# queso_dip_v4_5.net
KiCad netlist of a schematic drawn in EAGLE
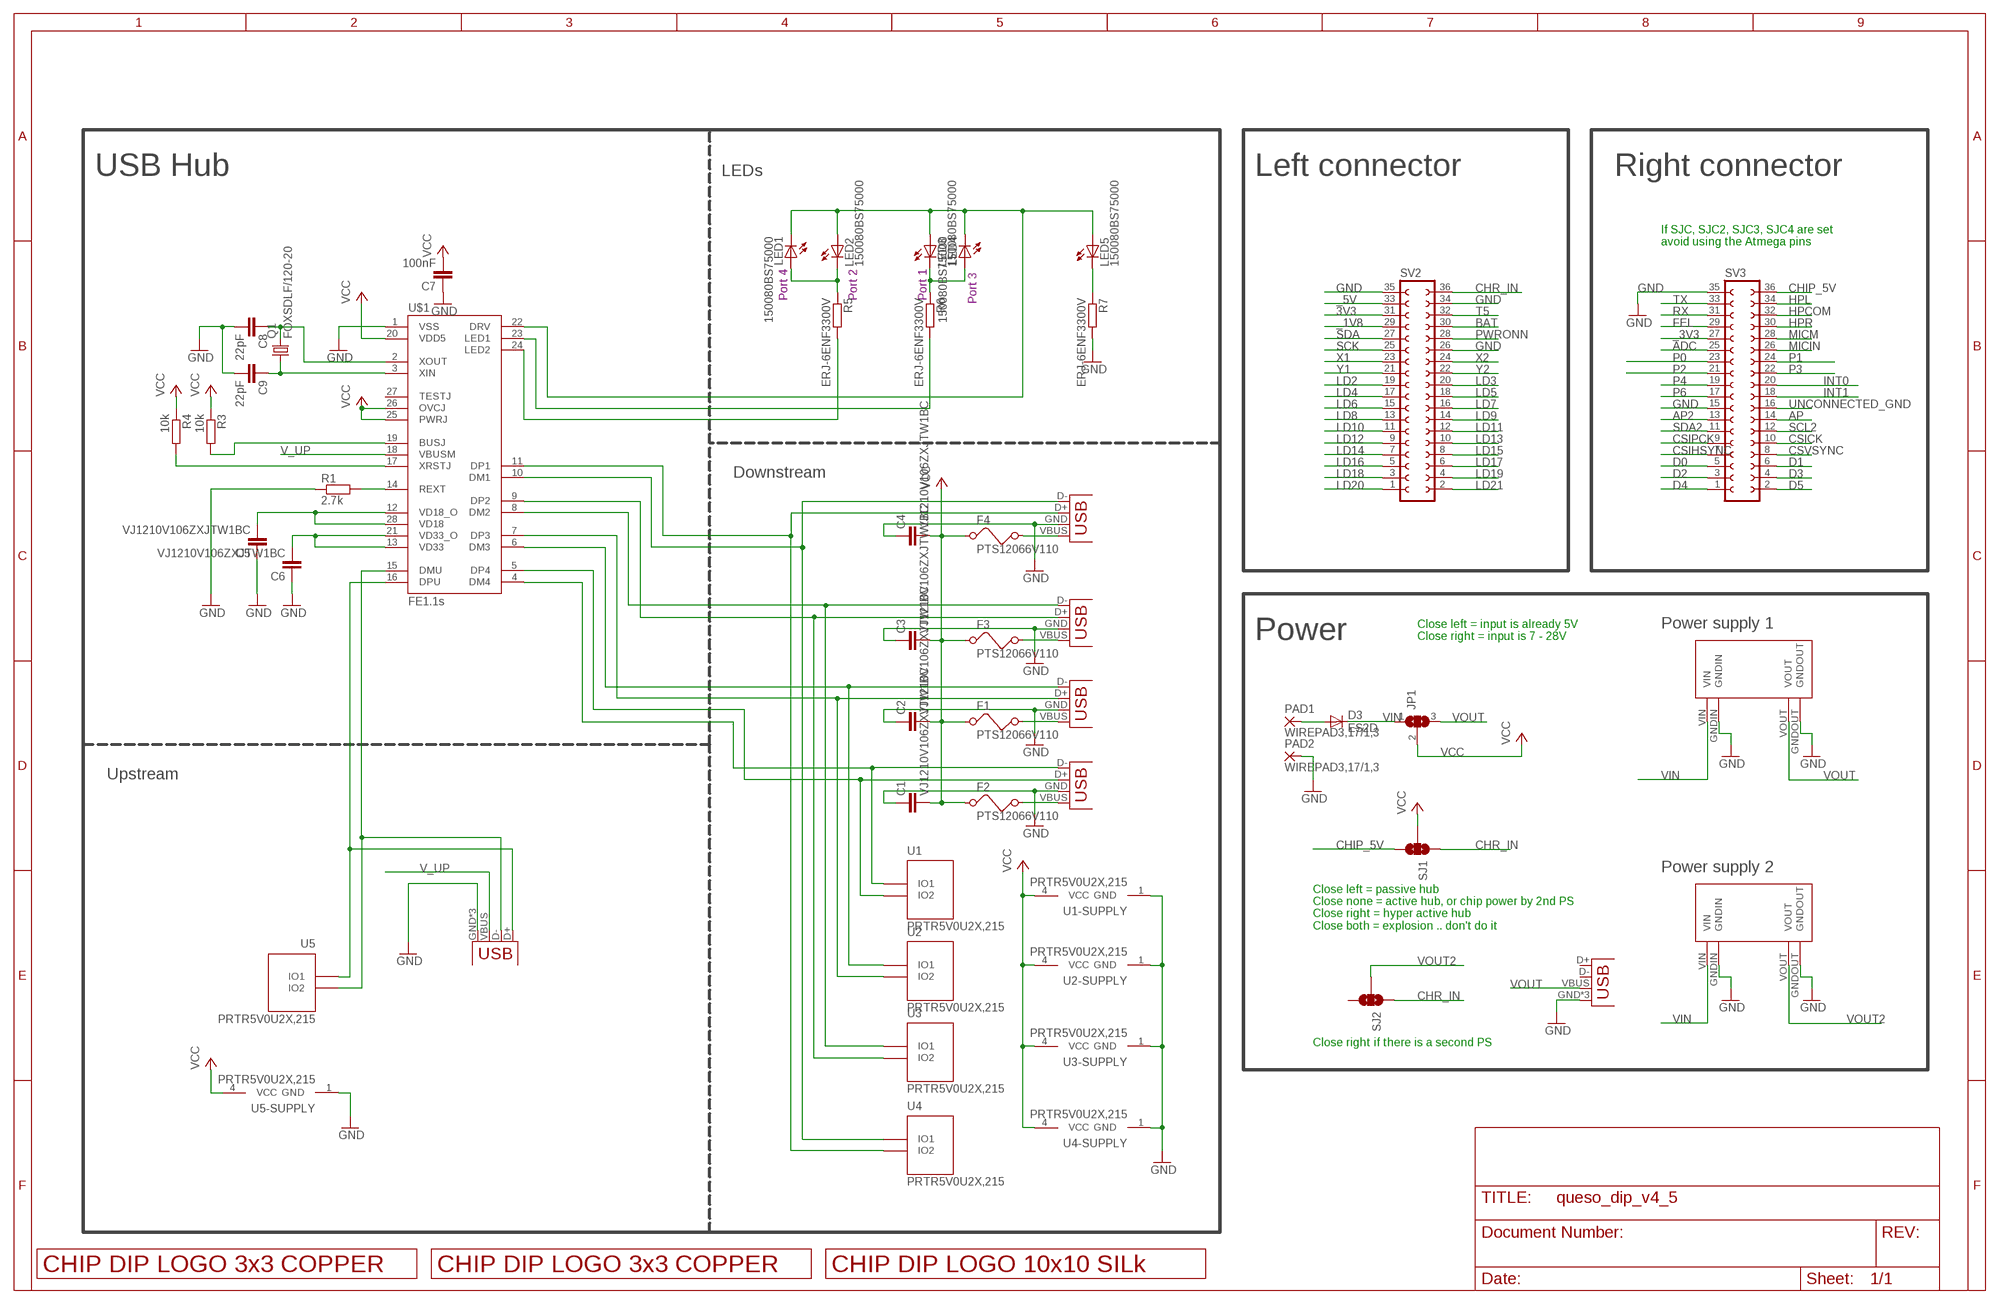
[diagram p0: schematic, sheet 1]

(export (version "E")
  (design (tool "Eeschema 10.0.6"))
  (components
    (comp (ref "C1")
      (value "VJ1210V106ZXJTW1BC")
      (footprint "eagle-import:C1210")
      (libsource (lib "eagle-import") (part "C-EUC1210"))
    )
    (comp (ref "C2")
      (value "VJ1210V106ZXJTW1BC")
      (footprint "eagle-import:C1210")
      (libsource (lib "eagle-import") (part "C-EUC1210"))
    )
    (comp (ref "C3")
      (value "VJ1210V106ZXJTW1BC")
      (footprint "eagle-import:C1210")
      (libsource (lib "eagle-import") (part "C-EUC1210"))
    )
    (comp (ref "C4")
      (value "VJ1210V106ZXJTW1BC")
      (footprint "eagle-import:C1210")
      (libsource (lib "eagle-import") (part "C-EUC1210"))
    )
    (comp (ref "C5")
      (value "VJ1210V106ZXJTW1BC")
      (footprint "eagle-import:C1210")
      (libsource (lib "eagle-import") (part "C-EUC1210"))
    )
    (comp (ref "C6")
      (value "VJ1210V106ZXJTW1BC")
      (footprint "eagle-import:C1210")
      (libsource (lib "eagle-import") (part "C-EUC1210"))
    )
    (comp (ref "C7")
      (value "100nF")
      (footprint "eagle-import:C0805")
      (libsource (lib "eagle-import") (part "C-EUC0805"))
    )
    (comp (ref "C8")
      (value "22pF")
      (footprint "eagle-import:C0805")
      (libsource (lib "eagle-import") (part "C-EUC0805"))
    )
    (comp (ref "C9")
      (value "22pF")
      (footprint "eagle-import:C0805")
      (libsource (lib "eagle-import") (part "C-EUC0805"))
    )
    (comp (ref "D3")
      (value "ES2D")
      (footprint "eagle-import:SMB")
      (libsource (lib "eagle-import") (part "ES2D"))
    )
    (comp (ref "F1")
      (value "PTS12066V110")
      (footprint "eagle-import:1210")
      (libsource (lib "eagle-import") (part "FUSED"))
    )
    (comp (ref "F2")
      (value "PTS12066V110")
      (footprint "eagle-import:1210")
      (libsource (lib "eagle-import") (part "FUSED"))
    )
    (comp (ref "F3")
      (value "PTS12066V110")
      (footprint "eagle-import:1210")
      (libsource (lib "eagle-import") (part "FUSED"))
    )
    (comp (ref "F4")
      (value "PTS12066V110")
      (footprint "eagle-import:1210")
      (libsource (lib "eagle-import") (part "FUSED"))
    )
    (comp (ref "JP1")
      (value "SJ2W")
      (footprint "eagle-import:SJ_2")
      (libsource (lib "eagle-import") (part "SJ2W"))
    )
    (comp (ref "LED1")
      (value "150080BS75000")
      (footprint "eagle-import:CHIP-LED0805")
      (libsource (lib "eagle-import") (part "LEDCHIP-LED0805"))
    )
    (comp (ref "LED2")
      (value "150080BS75000")
      (footprint "eagle-import:CHIP-LED0805")
      (libsource (lib "eagle-import") (part "LEDCHIP-LED0805"))
    )
    (comp (ref "LED3")
      (value "150080BS75000")
      (footprint "eagle-import:CHIP-LED0805")
      (libsource (lib "eagle-import") (part "LEDCHIP-LED0805"))
    )
    (comp (ref "LED4")
      (value "150080BS75000")
      (footprint "eagle-import:CHIP-LED0805")
      (libsource (lib "eagle-import") (part "LEDCHIP-LED0805"))
    )
    (comp (ref "LED5")
      (value "150080BS75000")
      (footprint "eagle-import:CHIP-LED0805")
      (libsource (lib "eagle-import") (part "LEDCHIP-LED0805"))
    )
    (comp (ref "PAD1")
      (value "WIREPAD3,17/1,3")
      (footprint "eagle-import:3,17_1,3")
      (libsource (lib "eagle-import") (part "WIREPAD3,17/1,3"))
    )
    (comp (ref "PAD2")
      (value "WIREPAD3,17/1,3")
      (footprint "eagle-import:3,17_1,3")
      (libsource (lib "eagle-import") (part "WIREPAD3,17/1,3"))
    )
    (comp (ref "Q1")
      (value "FOXSDLF/120-20")
      (footprint "eagle-import:SM49")
      (libsource (lib "eagle-import") (part "CRYSTALSM49"))
    )
    (comp (ref "R1")
      (value "2.7k")
      (footprint "eagle-import:R0805")
      (libsource (lib "eagle-import") (part "R-EU_R0805"))
    )
    (comp (ref "R3")
      (value "10k")
      (footprint "eagle-import:R0805")
      (libsource (lib "eagle-import") (part "R-EU_R0805"))
    )
    (comp (ref "R4")
      (value "10k")
      (footprint "eagle-import:R0805")
      (libsource (lib "eagle-import") (part "R-EU_R0805"))
    )
    (comp (ref "R5")
      (value "ERJ-6ENF3300V")
      (footprint "eagle-import:R0805")
      (libsource (lib "eagle-import") (part "R-EU_R0805"))
    )
    (comp (ref "R6")
      (value "ERJ-6ENF3300V")
      (footprint "eagle-import:R0805")
      (libsource (lib "eagle-import") (part "R-EU_R0805"))
    )
    (comp (ref "R7")
      (value "ERJ-6ENF3300V")
      (footprint "eagle-import:R0805")
      (libsource (lib "eagle-import") (part "R-EU_R0805"))
    )
    (comp (ref "SJ1")
      (value "SOLDERJUMPER_2WAYT")
      (footprint "eagle-import:SJ_2")
      (libsource (lib "eagle-import") (part "SOLDERJUMPER_2WAYT"))
    )
    (comp (ref "SJ2")
      (value "SOLDERJUMPER_2WAYT")
      (footprint "eagle-import:SJ_2")
      (libsource (lib "eagle-import") (part "SOLDERJUMPER_2WAYT"))
    )
    (comp (ref "SV2")
      (value "FE18-2")
      (footprint "eagle-import:FE18-2")
      (libsource (lib "eagle-import") (part "FE18-2"))
    )
    (comp (ref "SV3")
      (value "FE18-2")
      (footprint "eagle-import:FE18-2")
      (libsource (lib "eagle-import") (part "FE18-2"))
    )
    (comp (ref "U$1")
      (value "FE1.1S")
      (footprint "eagle-import:FE1.1S_SSOP-28")
      (libsource (lib "eagle-import") (part "FE1.1S"))
    )
    (comp (ref "U$2")
      (value "LOGO_3X3_COPPER")
      (footprint "eagle-import:LOGO_3X3_COPPER")
      (libsource (lib "eagle-import") (part "LOGO_3X3_COPPER"))
    )
    (comp (ref "U$3")
      (value "MP1584EN")
      (footprint "eagle-import:MP1584EN")
      (libsource (lib "eagle-import") (part "MP1584EN"))
    )
    (comp (ref "U$4")
      (value "LOGO_3X3_COPPER")
      (footprint "eagle-import:LOGO_3X3_COPPER")
      (libsource (lib "eagle-import") (part "LOGO_3X3_COPPER"))
    )
    (comp (ref "U$5")
      (value "LOGO_10X10_SILK")
      (footprint "eagle-import:LOGO_10X10_SILK")
      (libsource (lib "eagle-import") (part "LOGO_10X10_SILK"))
    )
    (comp (ref "U$9")
      (value "MP1584EN")
      (footprint "eagle-import:MP1584EN")
      (libsource (lib "eagle-import") (part "MP1584EN"))
    )
    (comp (ref "U1")
      (value "PRTR5V0U2X,215")
      (footprint "eagle-import:SOT-143B")
      (fields (field (name "MANUFACTURER") "NXP Semiconductors"))
      (libsource (lib "eagle-import") (part "PRTR5V0U2X?"))
    )
    (comp (ref "U2")
      (value "PRTR5V0U2X,215")
      (footprint "eagle-import:SOT-143B")
      (fields (field (name "MANUFACTURER") "NXP Semiconductors"))
      (libsource (lib "eagle-import") (part "PRTR5V0U2X?"))
    )
    (comp (ref "U3")
      (value "PRTR5V0U2X,215")
      (footprint "eagle-import:SOT-143B")
      (fields (field (name "MANUFACTURER") "NXP Semiconductors"))
      (libsource (lib "eagle-import") (part "PRTR5V0U2X?"))
    )
    (comp (ref "U4")
      (value "PRTR5V0U2X,215")
      (footprint "eagle-import:SOT-143B")
      (fields (field (name "MANUFACTURER") "NXP Semiconductors"))
      (libsource (lib "eagle-import") (part "PRTR5V0U2X?"))
    )
    (comp (ref "U5")
      (value "PRTR5V0U2X,215")
      (footprint "eagle-import:SOT-143B")
      (fields (field (name "MANUFACTURER") "NXP Semiconductors"))
      (libsource (lib "eagle-import") (part "PRTR5V0U2X?"))
    )
    (comp (ref "USB")
      (value "USBUSB-MICROB-SMT-DIP")
      (footprint "eagle-import:USB-MICROB-SMT-DIP")
      (libsource (lib "eagle-import") (part "USBUSB-MICROB-SMT-DIP"))
    )
    (comp (ref "USB1")
      (value "USBUSB-MICROB-SMT-DIP")
      (footprint "eagle-import:USB-MICROB-SMT-DIP")
      (libsource (lib "eagle-import") (part "USBUSB-MICROB-SMT-DIP"))
    )
    (comp (ref "X1")
      (value "USB-A-HU")
      (footprint "eagle-import:USB-A-HU")
      (libsource (lib "eagle-import") (part "USB-A-HU"))
    )
    (comp (ref "X2")
      (value "USB-A-HU")
      (footprint "eagle-import:USB-A-HU")
      (libsource (lib "eagle-import") (part "USB-A-HU"))
    )
    (comp (ref "X3")
      (value "USB-A-HU")
      (footprint "eagle-import:USB-A-HU")
      (libsource (lib "eagle-import") (part "USB-A-HU"))
    )
    (comp (ref "X4")
      (value "USB-A-HU")
      (footprint "eagle-import:USB-A-HU")
      (libsource (lib "eagle-import") (part "USB-A-HU"))
    )
  )
  (nets
    (net (code "1") (name "/3V3") (class "Default")
      (node (ref "SV2") (pin "31") (pinfunction "31_31") (pintype "passive"))
    )
    (net (code "2") (name "/ADC") (class "Default")
      (node (ref "SV3") (pin "25") (pinfunction "25_25") (pintype "passive"))
    )
    (net (code "3") (name "/AP") (class "Default")
      (node (ref "SV3") (pin "14") (pinfunction "14_14") (pintype "passive"))
    )
    (net (code "4") (name "/AP2") (class "Default")
      (node (ref "SV3") (pin "13") (pinfunction "13_13") (pintype "passive"))
    )
    (net (code "5") (name "/BAT") (class "Default")
      (node (ref "SV2") (pin "30") (pinfunction "30_30") (pintype "passive"))
    )
    (net (code "6") (name "/CHIP_5V") (class "Default")
      (node (ref "SJ1") (pin "3") (pinfunction "3_3") (pintype "passive"))
      (node (ref "SV3") (pin "36") (pinfunction "36_36") (pintype "passive"))
    )
    (net (code "7") (name "/CHR_IN") (class "Default")
      (node (ref "SJ1") (pin "1") (pinfunction "1_1") (pintype "passive"))
      (node (ref "SJ2") (pin "1") (pinfunction "1_1") (pintype "passive"))
      (node (ref "SV2") (pin "36") (pinfunction "36_36") (pintype "passive"))
    )
    (net (code "8") (name "/CSICK") (class "Default")
      (node (ref "SV3") (pin "10") (pinfunction "10_10") (pintype "passive"))
    )
    (net (code "9") (name "/CSIHSYNC") (class "Default")
      (node (ref "SV3") (pin "7") (pinfunction "7_7") (pintype "passive"))
    )
    (net (code "10") (name "/CSIPCK") (class "Default")
      (node (ref "SV3") (pin "9") (pinfunction "9_9") (pintype "passive"))
    )
    (net (code "11") (name "/CSVSYNC") (class "Default")
      (node (ref "SV3") (pin "8") (pinfunction "8_8") (pintype "passive"))
    )
    (net (code "12") (name "/D0") (class "Default")
      (node (ref "SV3") (pin "5") (pinfunction "5_5") (pintype "passive"))
    )
    (net (code "13") (name "/D1") (class "Default")
      (node (ref "SV3") (pin "6") (pinfunction "6_6") (pintype "passive"))
    )
    (net (code "14") (name "/D2") (class "Default")
      (node (ref "SV3") (pin "3") (pinfunction "3_3") (pintype "passive"))
    )
    (net (code "15") (name "/D3") (class "Default")
      (node (ref "SV3") (pin "4") (pinfunction "4_4") (pintype "passive"))
    )
    (net (code "16") (name "/D4") (class "Default")
      (node (ref "SV3") (pin "1") (pinfunction "1_1") (pintype "passive"))
    )
    (net (code "17") (name "/D5") (class "Default")
      (node (ref "SV3") (pin "2") (pinfunction "2_2") (pintype "passive"))
    )
    (net (code "18") (name "/FEL") (class "Default")
      (node (ref "SV3") (pin "29") (pinfunction "29_29") (pintype "passive"))
    )
    (net (code "19") (name "/HPCOM") (class "Default")
      (node (ref "SV3") (pin "32") (pinfunction "32_32") (pintype "passive"))
    )
    (net (code "20") (name "/HPL") (class "Default")
      (node (ref "SV3") (pin "34") (pinfunction "34_34") (pintype "passive"))
    )
    (net (code "21") (name "/HPR") (class "Default")
      (node (ref "SV3") (pin "30") (pinfunction "30_30") (pintype "passive"))
    )
    (net (code "22") (name "/INT0") (class "Default")
      (node (ref "SV3") (pin "20") (pinfunction "20_20") (pintype "passive"))
    )
    (net (code "23") (name "/INT1") (class "Default")
      (node (ref "SV3") (pin "18") (pinfunction "18_18") (pintype "passive"))
    )
    (net (code "24") (name "/LD2") (class "Default")
      (node (ref "SV2") (pin "19") (pinfunction "19_19") (pintype "passive"))
    )
    (net (code "25") (name "/LD3") (class "Default")
      (node (ref "SV2") (pin "20") (pinfunction "20_20") (pintype "passive"))
    )
    (net (code "26") (name "/LD4") (class "Default")
      (node (ref "SV2") (pin "17") (pinfunction "17_17") (pintype "passive"))
    )
    (net (code "27") (name "/LD5") (class "Default")
      (node (ref "SV2") (pin "18") (pinfunction "18_18") (pintype "passive"))
    )
    (net (code "28") (name "/LD6") (class "Default")
      (node (ref "SV2") (pin "15") (pinfunction "15_15") (pintype "passive"))
    )
    (net (code "29") (name "/LD7") (class "Default")
      (node (ref "SV2") (pin "16") (pinfunction "16_16") (pintype "passive"))
    )
    (net (code "30") (name "/LD8") (class "Default")
      (node (ref "SV2") (pin "13") (pinfunction "13_13") (pintype "passive"))
    )
    (net (code "31") (name "/LD9") (class "Default")
      (node (ref "SV2") (pin "14") (pinfunction "14_14") (pintype "passive"))
    )
    (net (code "32") (name "/LD10") (class "Default")
      (node (ref "SV2") (pin "11") (pinfunction "11_11") (pintype "passive"))
    )
    (net (code "33") (name "/LD11") (class "Default")
      (node (ref "SV2") (pin "12") (pinfunction "12_12") (pintype "passive"))
    )
    (net (code "34") (name "/LD12") (class "Default")
      (node (ref "SV2") (pin "9") (pinfunction "9_9") (pintype "passive"))
    )
    (net (code "35") (name "/LD13") (class "Default")
      (node (ref "SV2") (pin "10") (pinfunction "10_10") (pintype "passive"))
    )
    (net (code "36") (name "/LD14") (class "Default")
      (node (ref "SV2") (pin "7") (pinfunction "7_7") (pintype "passive"))
    )
    (net (code "37") (name "/LD15") (class "Default")
      (node (ref "SV2") (pin "8") (pinfunction "8_8") (pintype "passive"))
    )
    (net (code "38") (name "/LD16") (class "Default")
      (node (ref "SV2") (pin "5") (pinfunction "5_5") (pintype "passive"))
    )
    (net (code "39") (name "/LD17") (class "Default")
      (node (ref "SV2") (pin "6") (pinfunction "6_6") (pintype "passive"))
    )
    (net (code "40") (name "/LD18") (class "Default")
      (node (ref "SV2") (pin "3") (pinfunction "3_3") (pintype "passive"))
    )
    (net (code "41") (name "/LD19") (class "Default")
      (node (ref "SV2") (pin "4") (pinfunction "4_4") (pintype "passive"))
    )
    (net (code "42") (name "/LD20") (class "Default")
      (node (ref "SV2") (pin "1") (pinfunction "1_1") (pintype "passive"))
    )
    (net (code "43") (name "/LD21") (class "Default")
      (node (ref "SV2") (pin "2") (pinfunction "2_2") (pintype "passive"))
    )
    (net (code "44") (name "/MICIN") (class "Default")
      (node (ref "SV3") (pin "26") (pinfunction "26_26") (pintype "passive"))
    )
    (net (code "45") (name "/MICM") (class "Default")
      (node (ref "SV3") (pin "28") (pinfunction "28_28") (pintype "passive"))
    )
    (net (code "46") (name "/P0") (class "Default")
      (node (ref "SV3") (pin "23") (pinfunction "23_23") (pintype "passive"))
    )
    (net (code "47") (name "/P1") (class "Default")
      (node (ref "SV3") (pin "24") (pinfunction "24_24") (pintype "passive"))
    )
    (net (code "48") (name "/P2") (class "Default")
      (node (ref "SV3") (pin "21") (pinfunction "21_21") (pintype "passive"))
    )
    (net (code "49") (name "/P3") (class "Default")
      (node (ref "SV3") (pin "22") (pinfunction "22_22") (pintype "passive"))
    )
    (net (code "50") (name "/P4") (class "Default")
      (node (ref "SV3") (pin "19") (pinfunction "19_19") (pintype "passive"))
    )
    (net (code "51") (name "/P6") (class "Default")
      (node (ref "SV3") (pin "17") (pinfunction "17_17") (pintype "passive"))
    )
    (net (code "52") (name "/PWRONN") (class "Default")
      (node (ref "SV2") (pin "28") (pinfunction "28_28") (pintype "passive"))
    )
    (net (code "53") (name "/RX") (class "Default")
      (node (ref "SV3") (pin "31") (pinfunction "31_31") (pintype "passive"))
    )
    (net (code "54") (name "/SCK") (class "Default")
      (node (ref "SV2") (pin "25") (pinfunction "25_25") (pintype "passive"))
    )
    (net (code "55") (name "/SCL2") (class "Default")
      (node (ref "SV3") (pin "12") (pinfunction "12_12") (pintype "passive"))
    )
    (net (code "56") (name "/SDA") (class "Default")
      (node (ref "SV2") (pin "27") (pinfunction "27_27") (pintype "passive"))
    )
    (net (code "57") (name "/SDA2") (class "Default")
      (node (ref "SV3") (pin "11") (pinfunction "11_11") (pintype "passive"))
    )
    (net (code "58") (name "/T5") (class "Default")
      (node (ref "SV2") (pin "32") (pinfunction "32_32") (pintype "passive"))
    )
    (net (code "59") (name "/TX") (class "Default")
      (node (ref "SV3") (pin "33") (pinfunction "33_33") (pintype "passive"))
    )
    (net (code "60") (name "/UNCONNECTED_GND") (class "Default")
      (node (ref "SV3") (pin "16") (pinfunction "16_16") (pintype "passive"))
    )
    (net (code "61") (name "/VIN") (class "Default")
      (node (ref "D3") (pin "C") (pinfunction "C_C") (pintype "passive"))
      (node (ref "JP1") (pin "1") (pinfunction "1_1") (pintype "passive"))
      (node (ref "U$3") (pin "VIN") (pinfunction "VIN_VIN") (pintype "power_in"))
      (node (ref "U$9") (pin "VIN") (pinfunction "VIN_VIN") (pintype "power_in"))
    )
    (net (code "62") (name "/VOUT") (class "Default")
      (node (ref "JP1") (pin "3") (pinfunction "3_3") (pintype "passive"))
      (node (ref "U$9") (pin "VOUT") (pinfunction "VOUT_VOUT") (pintype "power_in"))
      (node (ref "USB1") (pin "VBUS") (pinfunction "VBUS_VBUS") (pintype "bidirectional"))
    )
    (net (code "63") (name "/VOUT2") (class "Default")
      (node (ref "SJ2") (pin "2") (pinfunction "2_2") (pintype "passive"))
      (node (ref "U$3") (pin "VOUT") (pinfunction "VOUT_VOUT") (pintype "power_in"))
    )
    (net (code "64") (name "/V_UP") (class "Default")
      (node (ref "U$1") (pin "18") (pinfunction "VBUSM_18") (pintype "bidirectional"))
      (node (ref "USB") (pin "VBUS") (pinfunction "VBUS_VBUS") (pintype "bidirectional"))
    )
    (net (code "65") (name "/X1") (class "Default")
      (node (ref "SV2") (pin "23") (pinfunction "23_23") (pintype "passive"))
    )
    (net (code "66") (name "/X2") (class "Default")
      (node (ref "SV2") (pin "24") (pinfunction "24_24") (pintype "passive"))
    )
    (net (code "67") (name "/Y1") (class "Default")
      (node (ref "SV2") (pin "21") (pinfunction "21_21") (pintype "passive"))
    )
    (net (code "68") (name "/Y2") (class "Default")
      (node (ref "SV2") (pin "22") (pinfunction "22_22") (pintype "passive"))
    )
    (net (code "69") (name "/_1V8") (class "Default")
      (node (ref "SV2") (pin "29") (pinfunction "29_29") (pintype "passive"))
    )
    (net (code "70") (name "/_3V3") (class "Default")
      (node (ref "SV3") (pin "27") (pinfunction "27_27") (pintype "passive"))
    )
    (net (code "71") (name "/_5V") (class "Default")
      (node (ref "SV2") (pin "33") (pinfunction "33_33") (pintype "passive"))
    )
    (net (code "72") (name "GND") (class "Default")
      (node (ref "C1") (pin "1") (pinfunction "1_1") (pintype "passive"))
      (node (ref "C2") (pin "1") (pinfunction "1_1") (pintype "passive"))
      (node (ref "C3") (pin "1") (pinfunction "1_1") (pintype "passive"))
      (node (ref "C4") (pin "1") (pinfunction "1_1") (pintype "passive"))
      (node (ref "C5") (pin "1") (pinfunction "1_1") (pintype "passive"))
      (node (ref "C6") (pin "1") (pinfunction "1_1") (pintype "passive"))
      (node (ref "C7") (pin "1") (pinfunction "1_1") (pintype "passive"))
      (node (ref "C8") (pin "2") (pinfunction "2_2") (pintype "passive"))
      (node (ref "C9") (pin "2") (pinfunction "2_2") (pintype "passive"))
      (node (ref "PAD2") (pin "1") (pinfunction "P_1") (pintype "passive"))
      (node (ref "R1") (pin "1") (pinfunction "1_1") (pintype "passive"))
      (node (ref "R7") (pin "2") (pinfunction "2_2") (pintype "passive"))
      (node (ref "SV2") (pin "26") (pinfunction "26_26") (pintype "passive"))
      (node (ref "SV2") (pin "34") (pinfunction "34_34") (pintype "passive"))
      (node (ref "SV2") (pin "35") (pinfunction "35_35") (pintype "passive"))
      (node (ref "SV3") (pin "15") (pinfunction "15_15") (pintype "passive"))
      (node (ref "SV3") (pin "35") (pinfunction "35_35") (pintype "passive"))
      (node (ref "U$1") (pin "1") (pinfunction "VSS_1") (pintype "bidirectional"))
      (node (ref "U$3") (pin "GNDIN") (pinfunction "GNDIN_GNDIN") (pintype "power_in"))
      (node (ref "U$3") (pin "GNDOUT") (pinfunction "GNDOUT_GNDOUT") (pintype "power_in"))
      (node (ref "U$9") (pin "GNDIN") (pinfunction "GNDIN_GNDIN") (pintype "power_in"))
      (node (ref "U$9") (pin "GNDOUT") (pinfunction "GNDOUT_GNDOUT") (pintype "power_in"))
      (node (ref "U1") (pin "1") (pinfunction "GND_1") (pintype "bidirectional"))
      (node (ref "U2") (pin "1") (pinfunction "GND_1") (pintype "bidirectional"))
      (node (ref "U3") (pin "1") (pinfunction "GND_1") (pintype "bidirectional"))
      (node (ref "U4") (pin "1") (pinfunction "GND_1") (pintype "bidirectional"))
      (node (ref "U5") (pin "1") (pinfunction "GND_1") (pintype "bidirectional"))
      (node (ref "USB") (pin "GND") (pinfunction "GND_GND") (pintype "bidirectional"))
      (node (ref "USB") (pin "MT1") (pinfunction "GND_MT1") (pintype "bidirectional"))
      (node (ref "USB") (pin "MT2") (pinfunction "GND_MT2") (pintype "bidirectional"))
      (node (ref "USB1") (pin "GND") (pinfunction "GND_GND") (pintype "bidirectional"))
      (node (ref "USB1") (pin "MT1") (pinfunction "GND_MT1") (pintype "bidirectional"))
      (node (ref "USB1") (pin "MT2") (pinfunction "GND_MT2") (pintype "bidirectional"))
      (node (ref "X1") (pin "GND") (pinfunction "VBUS_GND") (pintype "bidirectional"))
      (node (ref "X2") (pin "GND") (pinfunction "VBUS_GND") (pintype "bidirectional"))
      (node (ref "X3") (pin "GND") (pinfunction "VBUS_GND") (pintype "bidirectional"))
      (node (ref "X4") (pin "GND") (pinfunction "VBUS_GND") (pintype "bidirectional"))
    )
    (net (code "73") (name "Net-(LED1-PadA)") (class "Default")
      (node (ref "LED1") (pin "A") (pinfunction "A_A") (pintype "passive"))
      (node (ref "LED2") (pin "C") (pinfunction "C_C") (pintype "passive"))
      (node (ref "R5") (pin "1") (pinfunction "1_1") (pintype "passive"))
    )
    (net (code "74") (name "Net-(LED3-PadC)") (class "Default")
      (node (ref "LED3") (pin "C") (pinfunction "C_C") (pintype "passive"))
      (node (ref "LED4") (pin "A") (pinfunction "A_A") (pintype "passive"))
      (node (ref "R6") (pin "1") (pinfunction "1_1") (pintype "passive"))
    )
    (net (code "75") (name "Net-(LED5-PadC)") (class "Default")
      (node (ref "LED5") (pin "C") (pinfunction "C_C") (pintype "passive"))
      (node (ref "R7") (pin "1") (pinfunction "1_1") (pintype "passive"))
    )
    (net (code "76") (name "Net-(PAD1-P)") (class "Default")
      (node (ref "D3") (pin "A") (pinfunction "A_A") (pintype "passive"))
      (node (ref "PAD1") (pin "1") (pinfunction "P_1") (pintype "passive"))
    )
    (net (code "77") (name "Net-(U$1-BUSJ)") (class "Default")
      (node (ref "R3") (pin "2") (pinfunction "2_2") (pintype "passive"))
      (node (ref "U$1") (pin "19") (pinfunction "BUSJ_19") (pintype "bidirectional"))
    )
    (net (code "78") (name "Net-(U$1-DM1)") (class "Default")
      (node (ref "U$1") (pin "10") (pinfunction "DM1_10") (pintype "bidirectional"))
      (node (ref "U4") (pin "2") (pinfunction "IO1_2") (pintype "bidirectional"))
      (node (ref "X4") (pin "D-") (pinfunction "D+_D-") (pintype "bidirectional"))
    )
    (net (code "79") (name "Net-(U$1-DM2)") (class "Default")
      (node (ref "U$1") (pin "8") (pinfunction "DM2_8") (pintype "bidirectional"))
      (node (ref "U3") (pin "2") (pinfunction "IO1_2") (pintype "bidirectional"))
      (node (ref "X3") (pin "D-") (pinfunction "D+_D-") (pintype "bidirectional"))
    )
    (net (code "80") (name "Net-(U$1-DM3)") (class "Default")
      (node (ref "U$1") (pin "6") (pinfunction "DM3_6") (pintype "bidirectional"))
      (node (ref "U2") (pin "2") (pinfunction "IO1_2") (pintype "bidirectional"))
      (node (ref "X2") (pin "D-") (pinfunction "D+_D-") (pintype "bidirectional"))
    )
    (net (code "81") (name "Net-(U$1-DM4)") (class "Default")
      (node (ref "U$1") (pin "4") (pinfunction "DM4_4") (pintype "bidirectional"))
      (node (ref "U1") (pin "2") (pinfunction "IO1_2") (pintype "bidirectional"))
      (node (ref "X1") (pin "D-") (pinfunction "D+_D-") (pintype "bidirectional"))
    )
    (net (code "82") (name "Net-(U$1-DMU)") (class "Default")
      (node (ref "U$1") (pin "15") (pinfunction "DMU_15") (pintype "bidirectional"))
      (node (ref "U5") (pin "3") (pinfunction "IO2_3") (pintype "bidirectional"))
      (node (ref "USB") (pin "D-") (pinfunction "D-_D-") (pintype "bidirectional"))
    )
    (net (code "83") (name "Net-(U$1-DP1)") (class "Default")
      (node (ref "U$1") (pin "11") (pinfunction "DP1_11") (pintype "bidirectional"))
      (node (ref "U4") (pin "3") (pinfunction "IO2_3") (pintype "bidirectional"))
      (node (ref "X4") (pin "D+") (pinfunction "D-_D+") (pintype "bidirectional"))
    )
    (net (code "84") (name "Net-(U$1-DP2)") (class "Default")
      (node (ref "U$1") (pin "9") (pinfunction "DP2_9") (pintype "bidirectional"))
      (node (ref "U3") (pin "3") (pinfunction "IO2_3") (pintype "bidirectional"))
      (node (ref "X3") (pin "D+") (pinfunction "D-_D+") (pintype "bidirectional"))
    )
    (net (code "85") (name "Net-(U$1-DP3)") (class "Default")
      (node (ref "U$1") (pin "7") (pinfunction "DP3_7") (pintype "bidirectional"))
      (node (ref "U2") (pin "3") (pinfunction "IO2_3") (pintype "bidirectional"))
      (node (ref "X2") (pin "D+") (pinfunction "D-_D+") (pintype "bidirectional"))
    )
    (net (code "86") (name "Net-(U$1-DP4)") (class "Default")
      (node (ref "U$1") (pin "5") (pinfunction "DP4_5") (pintype "bidirectional"))
      (node (ref "U1") (pin "3") (pinfunction "IO2_3") (pintype "bidirectional"))
      (node (ref "X1") (pin "D+") (pinfunction "D-_D+") (pintype "bidirectional"))
    )
    (net (code "87") (name "Net-(U$1-DPU)") (class "Default")
      (node (ref "U$1") (pin "16") (pinfunction "DPU_16") (pintype "bidirectional"))
      (node (ref "U5") (pin "2") (pinfunction "IO1_2") (pintype "bidirectional"))
      (node (ref "USB") (pin "D+") (pinfunction "D+_D+") (pintype "bidirectional"))
    )
    (net (code "88") (name "Net-(U$1-DRV)") (class "Default")
      (node (ref "LED1") (pin "C") (pinfunction "C_C") (pintype "passive"))
      (node (ref "LED2") (pin "A") (pinfunction "A_A") (pintype "passive"))
      (node (ref "LED3") (pin "A") (pinfunction "A_A") (pintype "passive"))
      (node (ref "LED4") (pin "C") (pinfunction "C_C") (pintype "passive"))
      (node (ref "LED5") (pin "A") (pinfunction "A_A") (pintype "passive"))
      (node (ref "U$1") (pin "22") (pinfunction "DRV_22") (pintype "bidirectional"))
    )
    (net (code "89") (name "Net-(U$1-LED1)") (class "Default")
      (node (ref "R6") (pin "2") (pinfunction "2_2") (pintype "passive"))
      (node (ref "U$1") (pin "23") (pinfunction "LED1_23") (pintype "bidirectional"))
    )
    (net (code "90") (name "Net-(U$1-LED2)") (class "Default")
      (node (ref "R5") (pin "2") (pinfunction "2_2") (pintype "passive"))
      (node (ref "U$1") (pin "24") (pinfunction "LED2_24") (pintype "bidirectional"))
    )
    (net (code "91") (name "Net-(U$1-REXT)") (class "Default")
      (node (ref "R1") (pin "2") (pinfunction "2_2") (pintype "passive"))
      (node (ref "U$1") (pin "14") (pinfunction "REXT_14") (pintype "bidirectional"))
    )
    (net (code "92") (name "Net-(U$1-VD18)") (class "Default")
      (node (ref "C5") (pin "2") (pinfunction "2_2") (pintype "passive"))
      (node (ref "U$1") (pin "12") (pinfunction "VD18_O_12") (pintype "bidirectional"))
      (node (ref "U$1") (pin "28") (pinfunction "VD18_28") (pintype "bidirectional"))
    )
    (net (code "93") (name "Net-(U$1-VD33)") (class "Default")
      (node (ref "C6") (pin "2") (pinfunction "2_2") (pintype "passive"))
      (node (ref "U$1") (pin "13") (pinfunction "VD33_13") (pintype "bidirectional"))
      (node (ref "U$1") (pin "21") (pinfunction "VD33_O_21") (pintype "bidirectional"))
    )
    (net (code "94") (name "Net-(U$1-XIN)") (class "Default")
      (node (ref "C9") (pin "1") (pinfunction "1_1") (pintype "passive"))
      (node (ref "Q1") (pin "1") (pinfunction "1_1") (pintype "passive"))
      (node (ref "U$1") (pin "3") (pinfunction "XIN_3") (pintype "bidirectional"))
    )
    (net (code "95") (name "Net-(U$1-XOUT)") (class "Default")
      (node (ref "C8") (pin "1") (pinfunction "1_1") (pintype "passive"))
      (node (ref "Q1") (pin "2") (pinfunction "2_2") (pintype "passive"))
      (node (ref "U$1") (pin "2") (pinfunction "XOUT_2") (pintype "bidirectional"))
    )
    (net (code "96") (name "Net-(U$1-XRSTJ)") (class "Default")
      (node (ref "R4") (pin "2") (pinfunction "2_2") (pintype "passive"))
      (node (ref "U$1") (pin "17") (pinfunction "XRSTJ_17") (pintype "bidirectional"))
    )
    (net (code "97") (name "Net-(X1-GND)") (class "Default")
      (node (ref "F2") (pin "2") (pinfunction "2_2") (pintype "passive"))
      (node (ref "X1") (pin "VBUS") (pinfunction "GND_VBUS") (pintype "bidirectional"))
    )
    (net (code "98") (name "Net-(X2-GND)") (class "Default")
      (node (ref "F1") (pin "2") (pinfunction "2_2") (pintype "passive"))
      (node (ref "X2") (pin "VBUS") (pinfunction "GND_VBUS") (pintype "bidirectional"))
    )
    (net (code "99") (name "Net-(X3-GND)") (class "Default")
      (node (ref "F3") (pin "2") (pinfunction "2_2") (pintype "passive"))
      (node (ref "X3") (pin "VBUS") (pinfunction "GND_VBUS") (pintype "bidirectional"))
    )
    (net (code "100") (name "Net-(X4-GND)") (class "Default")
      (node (ref "F4") (pin "2") (pinfunction "2_2") (pintype "passive"))
      (node (ref "X4") (pin "VBUS") (pinfunction "GND_VBUS") (pintype "bidirectional"))
    )
    (net (code "101") (name "VCC") (class "Default")
      (node (ref "C1") (pin "2") (pinfunction "2_2") (pintype "passive"))
      (node (ref "C2") (pin "2") (pinfunction "2_2") (pintype "passive"))
      (node (ref "C3") (pin "2") (pinfunction "2_2") (pintype "passive"))
      (node (ref "C4") (pin "2") (pinfunction "2_2") (pintype "passive"))
      (node (ref "C7") (pin "2") (pinfunction "2_2") (pintype "passive"))
      (node (ref "F1") (pin "1") (pinfunction "1_1") (pintype "passive"))
      (node (ref "F2") (pin "1") (pinfunction "1_1") (pintype "passive"))
      (node (ref "F3") (pin "1") (pinfunction "1_1") (pintype "passive"))
      (node (ref "F4") (pin "1") (pinfunction "1_1") (pintype "passive"))
      (node (ref "JP1") (pin "2") (pinfunction "2_2") (pintype "passive"))
      (node (ref "R3") (pin "1") (pinfunction "1_1") (pintype "passive"))
      (node (ref "R4") (pin "1") (pinfunction "1_1") (pintype "passive"))
      (node (ref "SJ1") (pin "2") (pinfunction "2_2") (pintype "passive"))
      (node (ref "U$1") (pin "20") (pinfunction "VDD5_20") (pintype "bidirectional"))
      (node (ref "U$1") (pin "25") (pinfunction "PWRJ_25") (pintype "bidirectional"))
      (node (ref "U$1") (pin "26") (pinfunction "OVCJ_26") (pintype "bidirectional"))
      (node (ref "U1") (pin "4") (pinfunction "VCC_4") (pintype "bidirectional"))
      (node (ref "U2") (pin "4") (pinfunction "VCC_4") (pintype "bidirectional"))
      (node (ref "U3") (pin "4") (pinfunction "VCC_4") (pintype "bidirectional"))
      (node (ref "U4") (pin "4") (pinfunction "VCC_4") (pintype "bidirectional"))
      (node (ref "U5") (pin "4") (pinfunction "VCC_4") (pintype "bidirectional"))
    )
    (net (code "102") (name "unconnected-(SJ2-Pad3)") (class "Default")
      (node (ref "SJ2") (pin "3") (pinfunction "3_3") (pintype "passive"))
    )
    (net (code "103") (name "unconnected-(U$1-TESTJ-Pad27)") (class "Default")
      (node (ref "U$1") (pin "27") (pinfunction "TESTJ_27") (pintype "bidirectional"))
    )
    (net (code "104") (name "unconnected-(USB1-PadD+)") (class "Default")
      (node (ref "USB1") (pin "D+") (pinfunction "D+_D+") (pintype "bidirectional"))
    )
    (net (code "105") (name "unconnected-(USB1-PadD-)") (class "Default")
      (node (ref "USB1") (pin "D-") (pinfunction "D-_D-") (pintype "bidirectional"))
    )
  )
)
